# 88__3.net
KiCad netlist of a schematic drawn in Altium Designer
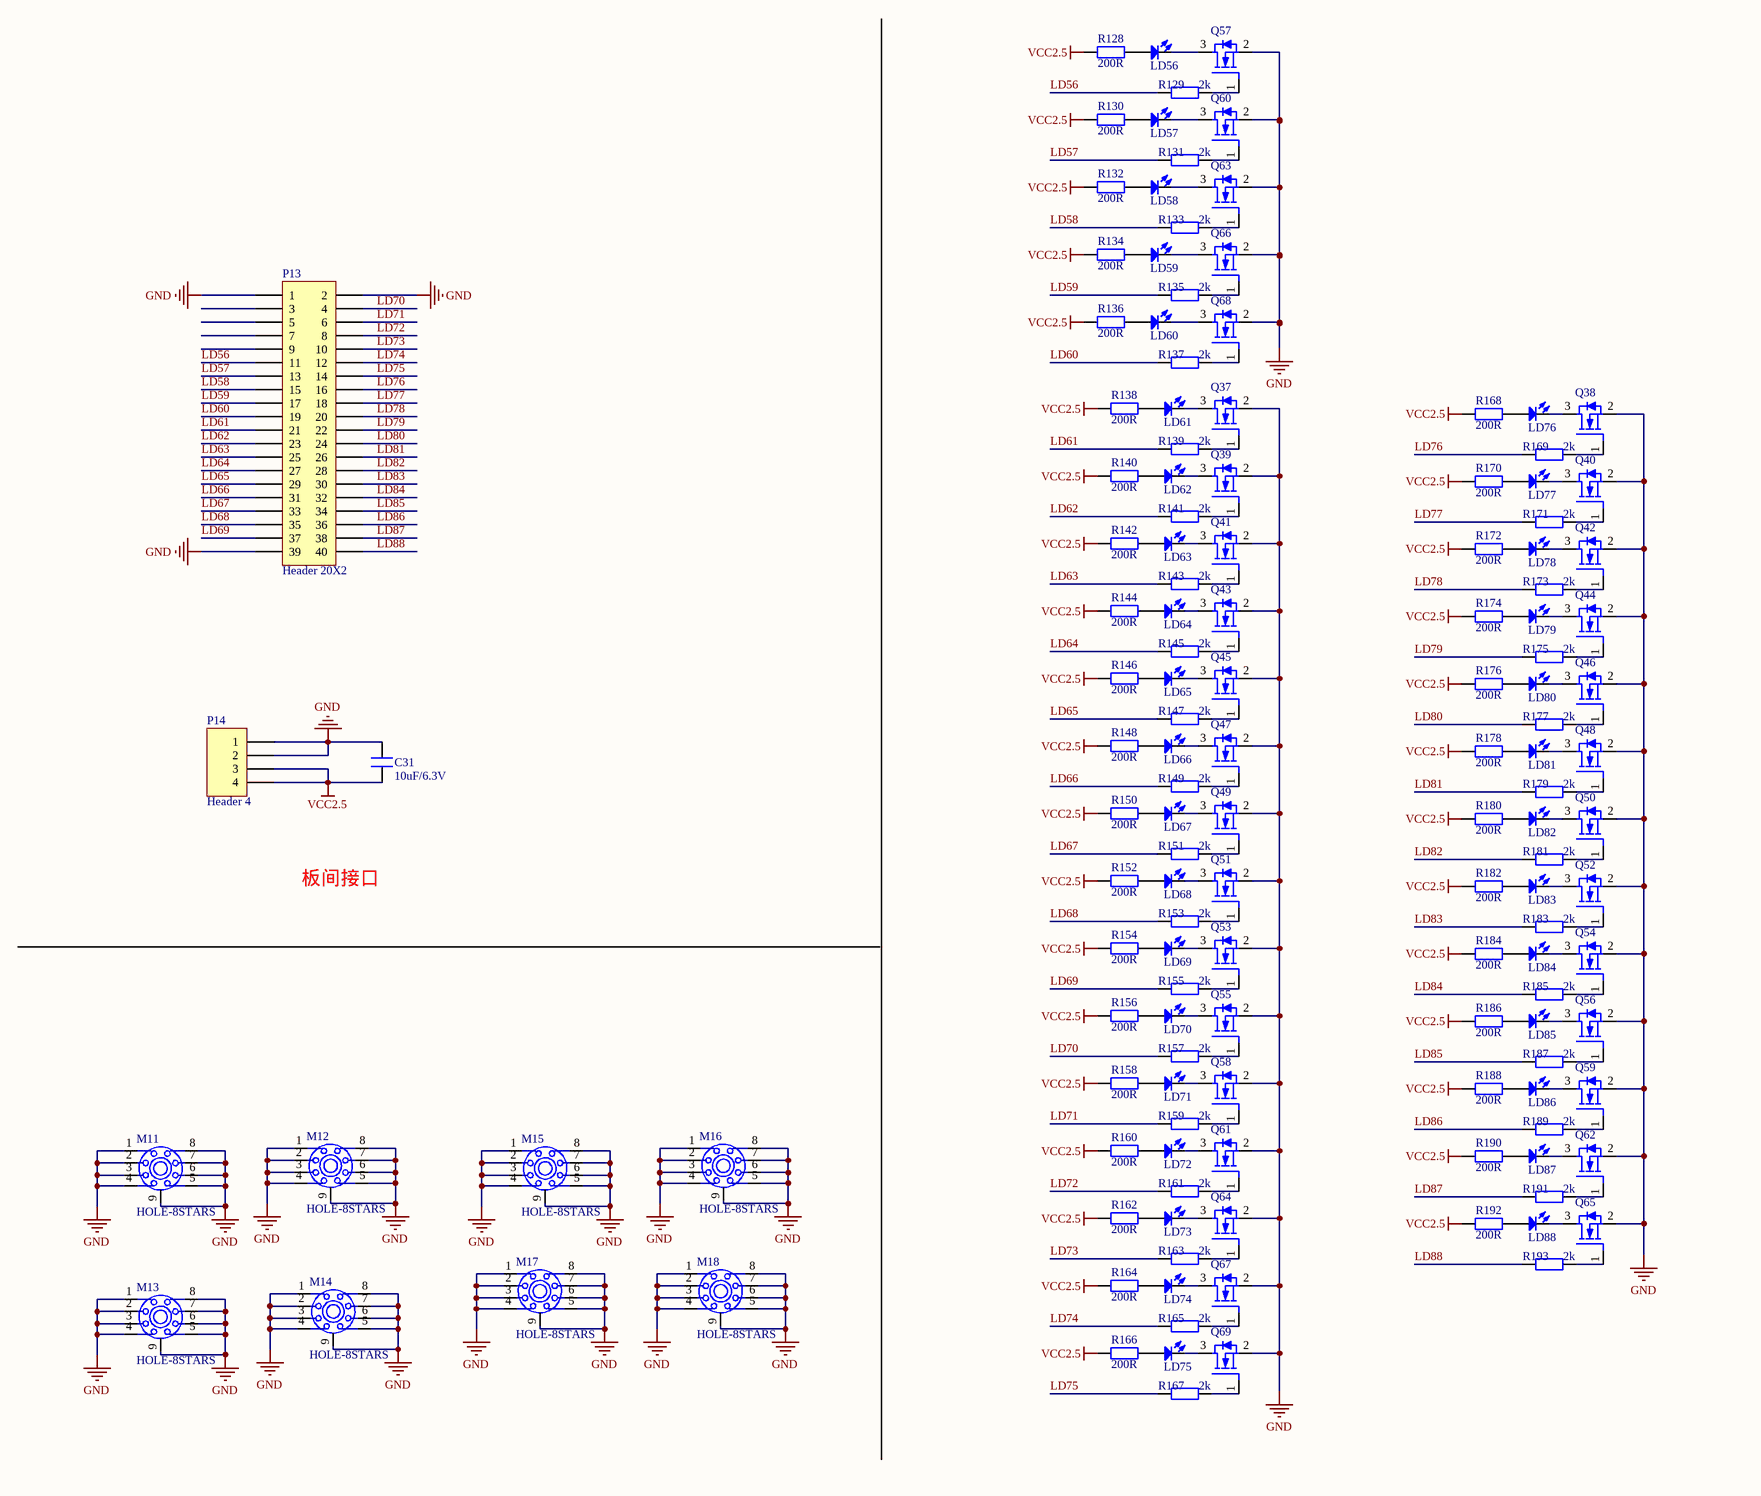
[diagram p0: 88路激光器工程_3.SchDoc, bottom]

(export (version "E")
  (design (tool "Eeschema 10.0.6"))
  (components
    (comp (ref "C31")
      (value "10uF/6.3V")
      (footprint "C0805")
      (libsource (lib "Explorer STM32F407封装库2") (part "C"))
    )
    (comp (ref "LD56") (value "LD") (footprint "LD_3P") (libsource (lib "SchLib1") (part "LD")))
    (comp (ref "LD57") (value "LD") (footprint "LD_3P") (libsource (lib "SchLib1") (part "LD")))
    (comp (ref "LD58") (value "LD") (footprint "LD_3P") (libsource (lib "SchLib1") (part "LD")))
    (comp (ref "LD59") (value "LD") (footprint "LD_3P") (libsource (lib "SchLib1") (part "LD")))
    (comp (ref "LD60") (value "LD") (footprint "LD_3P") (libsource (lib "SchLib1") (part "LD")))
    (comp (ref "LD61") (value "LD") (footprint "LD_3P") (libsource (lib "SchLib1") (part "LD")))
    (comp (ref "LD62") (value "LD") (footprint "LD_3P") (libsource (lib "SchLib1") (part "LD")))
    (comp (ref "LD63") (value "LD") (footprint "LD_3P") (libsource (lib "SchLib1") (part "LD")))
    (comp (ref "LD64") (value "LD") (footprint "LD_3P") (libsource (lib "SchLib1") (part "LD")))
    (comp (ref "LD65") (value "LD") (footprint "LD_3P") (libsource (lib "SchLib1") (part "LD")))
    (comp (ref "LD66") (value "LD") (footprint "LD_3P") (libsource (lib "SchLib1") (part "LD")))
    (comp (ref "LD67") (value "LD") (footprint "LD_3P") (libsource (lib "SchLib1") (part "LD")))
    (comp (ref "LD68") (value "LD") (footprint "LD_3P") (libsource (lib "SchLib1") (part "LD")))
    (comp (ref "LD69") (value "LD") (footprint "LD_3P") (libsource (lib "SchLib1") (part "LD")))
    (comp (ref "LD70") (value "LD") (footprint "LD_3P") (libsource (lib "SchLib1") (part "LD")))
    (comp (ref "LD71") (value "LD") (footprint "LD_3P") (libsource (lib "SchLib1") (part "LD")))
    (comp (ref "LD72") (value "LD") (footprint "LD_3P") (libsource (lib "SchLib1") (part "LD")))
    (comp (ref "LD73") (value "LD") (footprint "LD_3P") (libsource (lib "SchLib1") (part "LD")))
    (comp (ref "LD74") (value "LD") (footprint "LD_3P") (libsource (lib "SchLib1") (part "LD")))
    (comp (ref "LD75") (value "LD") (footprint "LD_3P") (libsource (lib "SchLib1") (part "LD")))
    (comp (ref "LD76") (value "LD") (footprint "LD_3P") (libsource (lib "SchLib1") (part "LD")))
    (comp (ref "LD77") (value "LD") (footprint "LD_3P") (libsource (lib "SchLib1") (part "LD")))
    (comp (ref "LD78") (value "LD") (footprint "LD_3P") (libsource (lib "SchLib1") (part "LD")))
    (comp (ref "LD79") (value "LD") (footprint "LD_3P") (libsource (lib "SchLib1") (part "LD")))
    (comp (ref "LD80") (value "LD") (footprint "LD_3P") (libsource (lib "SchLib1") (part "LD")))
    (comp (ref "LD81") (value "LD") (footprint "LD_3P") (libsource (lib "SchLib1") (part "LD")))
    (comp (ref "LD82") (value "LD") (footprint "LD_3P") (libsource (lib "SchLib1") (part "LD")))
    (comp (ref "LD83") (value "LD") (footprint "LD_3P") (libsource (lib "SchLib1") (part "LD")))
    (comp (ref "LD84") (value "LD") (footprint "LD_3P") (libsource (lib "SchLib1") (part "LD")))
    (comp (ref "LD85") (value "LD") (footprint "LD_3P") (libsource (lib "SchLib1") (part "LD")))
    (comp (ref "LD86") (value "LD") (footprint "LD_3P") (libsource (lib "SchLib1") (part "LD")))
    (comp (ref "LD87") (value "LD") (footprint "LD_3P") (libsource (lib "SchLib1") (part "LD")))
    (comp (ref "LD88") (value "LD") (footprint "LD_3P") (libsource (lib "SchLib1") (part "LD")))
    (comp (ref "M11")
      (value "HOLE-8STARS")
      (footprint "HOLE_3MM")
      (libsource (lib "TOF_SCH") (part "HOLE-8STARS"))
    )
    (comp (ref "M12")
      (value "HOLE-8STARS")
      (footprint "HOLE_3MM")
      (libsource (lib "TOF_SCH") (part "HOLE-8STARS"))
    )
    (comp (ref "M13")
      (value "HOLE-8STARS")
      (footprint "HOLE_3MM")
      (libsource (lib "TOF_SCH") (part "HOLE-8STARS"))
    )
    (comp (ref "M14")
      (value "HOLE-8STARS")
      (footprint "HOLE_3MM")
      (libsource (lib "TOF_SCH") (part "HOLE-8STARS"))
    )
    (comp (ref "M15")
      (value "HOLE-8STARS")
      (footprint "HOLE_3MM")
      (libsource (lib "TOF_SCH") (part "HOLE-8STARS"))
    )
    (comp (ref "M16")
      (value "HOLE-8STARS")
      (footprint "HOLE_3MM")
      (libsource (lib "TOF_SCH") (part "HOLE-8STARS"))
    )
    (comp (ref "M17")
      (value "HOLE-8STARS")
      (footprint "HOLE_3MM")
      (libsource (lib "TOF_SCH") (part "HOLE-8STARS"))
    )
    (comp (ref "M18")
      (value "HOLE-8STARS")
      (footprint "HOLE_3MM")
      (libsource (lib "TOF_SCH") (part "HOLE-8STARS"))
    )
    (comp (ref "P13")
      (value "Header 20X2")
      (footprint "JATG_2.0mm_2x20P_SMD")
      (description "Header, 20-Pin, Dual row")
      (fields (field (name "PUBLISHER") "Altium Limited"))
      (libsource (lib "Miscellaneous Connectors") (part "Header 20X2"))
    )
    (comp (ref "P14")
      (value "Header 4")
      (footprint "XH2.54MM_4P_立式")
      (description "Header, 4-Pin")
      (fields (field (name "PUBLISHER") "Altium Limited"))
      (libsource (lib "Miscellaneous Connectors") (part "Header 4"))
    )
    (comp (ref "Q37") (value "NMOS") (footprint "SOT23-3") (libsource (lib "88路激光器工程") (part "NMOS")))
    (comp (ref "Q38") (value "NMOS") (footprint "SOT23-3") (libsource (lib "88路激光器工程") (part "NMOS")))
    (comp (ref "Q39") (value "NMOS") (footprint "SOT23-3") (libsource (lib "88路激光器工程") (part "NMOS")))
    (comp (ref "Q40") (value "NMOS") (footprint "SOT23-3") (libsource (lib "88路激光器工程") (part "NMOS")))
    (comp (ref "Q41") (value "NMOS") (footprint "SOT23-3") (libsource (lib "88路激光器工程") (part "NMOS")))
    (comp (ref "Q42") (value "NMOS") (footprint "SOT23-3") (libsource (lib "88路激光器工程") (part "NMOS")))
    (comp (ref "Q43") (value "NMOS") (footprint "SOT23-3") (libsource (lib "88路激光器工程") (part "NMOS")))
    (comp (ref "Q44") (value "NMOS") (footprint "SOT23-3") (libsource (lib "88路激光器工程") (part "NMOS")))
    (comp (ref "Q45") (value "NMOS") (footprint "SOT23-3") (libsource (lib "88路激光器工程") (part "NMOS")))
    (comp (ref "Q46") (value "NMOS") (footprint "SOT23-3") (libsource (lib "88路激光器工程") (part "NMOS")))
    (comp (ref "Q47") (value "NMOS") (footprint "SOT23-3") (libsource (lib "88路激光器工程") (part "NMOS")))
    (comp (ref "Q48") (value "NMOS") (footprint "SOT23-3") (libsource (lib "88路激光器工程") (part "NMOS")))
    (comp (ref "Q49") (value "NMOS") (footprint "SOT23-3") (libsource (lib "88路激光器工程") (part "NMOS")))
    (comp (ref "Q50") (value "NMOS") (footprint "SOT23-3") (libsource (lib "88路激光器工程") (part "NMOS")))
    (comp (ref "Q51") (value "NMOS") (footprint "SOT23-3") (libsource (lib "88路激光器工程") (part "NMOS")))
    (comp (ref "Q52") (value "NMOS") (footprint "SOT23-3") (libsource (lib "88路激光器工程") (part "NMOS")))
    (comp (ref "Q53") (value "NMOS") (footprint "SOT23-3") (libsource (lib "88路激光器工程") (part "NMOS")))
    (comp (ref "Q54") (value "NMOS") (footprint "SOT23-3") (libsource (lib "88路激光器工程") (part "NMOS")))
    (comp (ref "Q55") (value "NMOS") (footprint "SOT23-3") (libsource (lib "88路激光器工程") (part "NMOS")))
    (comp (ref "Q56") (value "NMOS") (footprint "SOT23-3") (libsource (lib "88路激光器工程") (part "NMOS")))
    (comp (ref "Q57") (value "NMOS") (footprint "SOT23-3") (libsource (lib "88路激光器工程") (part "NMOS")))
    (comp (ref "Q58") (value "NMOS") (footprint "SOT23-3") (libsource (lib "88路激光器工程") (part "NMOS")))
    (comp (ref "Q59") (value "NMOS") (footprint "SOT23-3") (libsource (lib "88路激光器工程") (part "NMOS")))
    (comp (ref "Q60") (value "NMOS") (footprint "SOT23-3") (libsource (lib "88路激光器工程") (part "NMOS")))
    (comp (ref "Q61") (value "NMOS") (footprint "SOT23-3") (libsource (lib "88路激光器工程") (part "NMOS")))
    (comp (ref "Q62") (value "NMOS") (footprint "SOT23-3") (libsource (lib "88路激光器工程") (part "NMOS")))
    (comp (ref "Q63") (value "NMOS") (footprint "SOT23-3") (libsource (lib "88路激光器工程") (part "NMOS")))
    (comp (ref "Q64") (value "NMOS") (footprint "SOT23-3") (libsource (lib "88路激光器工程") (part "NMOS")))
    (comp (ref "Q65") (value "NMOS") (footprint "SOT23-3") (libsource (lib "88路激光器工程") (part "NMOS")))
    (comp (ref "Q66") (value "NMOS") (footprint "SOT23-3") (libsource (lib "88路激光器工程") (part "NMOS")))
    (comp (ref "Q67") (value "NMOS") (footprint "SOT23-3") (libsource (lib "88路激光器工程") (part "NMOS")))
    (comp (ref "Q68") (value "NMOS") (footprint "SOT23-3") (libsource (lib "88路激光器工程") (part "NMOS")))
    (comp (ref "Q69") (value "NMOS") (footprint "SOT23-3") (libsource (lib "88路激光器工程") (part "NMOS")))
    (comp (ref "R128")
      (value "200R")
      (footprint "R0805")
      (description "Resistor")
      (fields (field (name "PUBLISHER") "Altium Limited"))
      (libsource (lib "Miscellaneous Devices") (part "Res2"))
    )
    (comp (ref "R129")
      (value "2k")
      (footprint "R0805")
      (description "Resistor")
      (fields (field (name "PUBLISHER") "Altium Limited"))
      (libsource (lib "Miscellaneous Devices") (part "Res2"))
    )
    (comp (ref "R130")
      (value "200R")
      (footprint "R0805")
      (description "Resistor")
      (fields (field (name "PUBLISHER") "Altium Limited"))
      (libsource (lib "Miscellaneous Devices") (part "Res2"))
    )
    (comp (ref "R131")
      (value "2k")
      (footprint "R0805")
      (description "Resistor")
      (fields (field (name "PUBLISHER") "Altium Limited"))
      (libsource (lib "Miscellaneous Devices") (part "Res2"))
    )
    (comp (ref "R132")
      (value "200R")
      (footprint "R0805")
      (description "Resistor")
      (fields (field (name "PUBLISHER") "Altium Limited"))
      (libsource (lib "Miscellaneous Devices") (part "Res2"))
    )
    (comp (ref "R133")
      (value "2k")
      (footprint "R0805")
      (description "Resistor")
      (fields (field (name "PUBLISHER") "Altium Limited"))
      (libsource (lib "Miscellaneous Devices") (part "Res2"))
    )
    (comp (ref "R134")
      (value "200R")
      (footprint "R0805")
      (description "Resistor")
      (fields (field (name "PUBLISHER") "Altium Limited"))
      (libsource (lib "Miscellaneous Devices") (part "Res2"))
    )
    (comp (ref "R135")
      (value "2k")
      (footprint "R0805")
      (description "Resistor")
      (fields (field (name "PUBLISHER") "Altium Limited"))
      (libsource (lib "Miscellaneous Devices") (part "Res2"))
    )
    (comp (ref "R136")
      (value "200R")
      (footprint "R0805")
      (description "Resistor")
      (fields (field (name "PUBLISHER") "Altium Limited"))
      (libsource (lib "Miscellaneous Devices") (part "Res2"))
    )
    (comp (ref "R137")
      (value "2k")
      (footprint "R0805")
      (description "Resistor")
      (fields (field (name "PUBLISHER") "Altium Limited"))
      (libsource (lib "Miscellaneous Devices") (part "Res2"))
    )
    (comp (ref "R138")
      (value "200R")
      (footprint "R0805")
      (description "Resistor")
      (fields (field (name "PUBLISHER") "Altium Limited"))
      (libsource (lib "Miscellaneous Devices") (part "Res2"))
    )
    (comp (ref "R139")
      (value "2k")
      (footprint "R0805")
      (description "Resistor")
      (fields (field (name "PUBLISHER") "Altium Limited"))
      (libsource (lib "Miscellaneous Devices") (part "Res2"))
    )
    (comp (ref "R140")
      (value "200R")
      (footprint "R0805")
      (description "Resistor")
      (fields (field (name "PUBLISHER") "Altium Limited"))
      (libsource (lib "Miscellaneous Devices") (part "Res2"))
    )
    (comp (ref "R141")
      (value "2k")
      (footprint "R0805")
      (description "Resistor")
      (fields (field (name "PUBLISHER") "Altium Limited"))
      (libsource (lib "Miscellaneous Devices") (part "Res2"))
    )
    (comp (ref "R142")
      (value "200R")
      (footprint "R0805")
      (description "Resistor")
      (fields (field (name "PUBLISHER") "Altium Limited"))
      (libsource (lib "Miscellaneous Devices") (part "Res2"))
    )
    (comp (ref "R143")
      (value "2k")
      (footprint "R0805")
      (description "Resistor")
      (fields (field (name "PUBLISHER") "Altium Limited"))
      (libsource (lib "Miscellaneous Devices") (part "Res2"))
    )
    (comp (ref "R144")
      (value "200R")
      (footprint "R0805")
      (description "Resistor")
      (fields (field (name "PUBLISHER") "Altium Limited"))
      (libsource (lib "Miscellaneous Devices") (part "Res2"))
    )
    (comp (ref "R145")
      (value "2k")
      (footprint "R0805")
      (description "Resistor")
      (fields (field (name "PUBLISHER") "Altium Limited"))
      (libsource (lib "Miscellaneous Devices") (part "Res2"))
    )
    (comp (ref "R146")
      (value "200R")
      (footprint "R0805")
      (description "Resistor")
      (fields (field (name "PUBLISHER") "Altium Limited"))
      (libsource (lib "Miscellaneous Devices") (part "Res2"))
    )
    (comp (ref "R147")
      (value "2k")
      (footprint "R0805")
      (description "Resistor")
      (fields (field (name "PUBLISHER") "Altium Limited"))
      (libsource (lib "Miscellaneous Devices") (part "Res2"))
    )
    (comp (ref "R148")
      (value "200R")
      (footprint "R0805")
      (description "Resistor")
      (fields (field (name "PUBLISHER") "Altium Limited"))
      (libsource (lib "Miscellaneous Devices") (part "Res2"))
    )
    (comp (ref "R149")
      (value "2k")
      (footprint "R0805")
      (description "Resistor")
      (fields (field (name "PUBLISHER") "Altium Limited"))
      (libsource (lib "Miscellaneous Devices") (part "Res2"))
    )
    (comp (ref "R150")
      (value "200R")
      (footprint "R0805")
      (description "Resistor")
      (fields (field (name "PUBLISHER") "Altium Limited"))
      (libsource (lib "Miscellaneous Devices") (part "Res2"))
    )
    (comp (ref "R151")
      (value "2k")
      (footprint "R0805")
      (description "Resistor")
      (fields (field (name "PUBLISHER") "Altium Limited"))
      (libsource (lib "Miscellaneous Devices") (part "Res2"))
    )
    (comp (ref "R152")
      (value "200R")
      (footprint "R0805")
      (description "Resistor")
      (fields (field (name "PUBLISHER") "Altium Limited"))
      (libsource (lib "Miscellaneous Devices") (part "Res2"))
    )
    (comp (ref "R153")
      (value "2k")
      (footprint "R0805")
      (description "Resistor")
      (fields (field (name "PUBLISHER") "Altium Limited"))
      (libsource (lib "Miscellaneous Devices") (part "Res2"))
    )
    (comp (ref "R154")
      (value "200R")
      (footprint "R0805")
      (description "Resistor")
      (fields (field (name "PUBLISHER") "Altium Limited"))
      (libsource (lib "Miscellaneous Devices") (part "Res2"))
    )
    (comp (ref "R155")
      (value "2k")
      (footprint "R0805")
      (description "Resistor")
      (fields (field (name "PUBLISHER") "Altium Limited"))
      (libsource (lib "Miscellaneous Devices") (part "Res2"))
    )
    (comp (ref "R156")
      (value "200R")
      (footprint "R0805")
      (description "Resistor")
      (fields (field (name "PUBLISHER") "Altium Limited"))
      (libsource (lib "Miscellaneous Devices") (part "Res2"))
    )
    (comp (ref "R157")
      (value "2k")
      (footprint "R0805")
      (description "Resistor")
      (fields (field (name "PUBLISHER") "Altium Limited"))
      (libsource (lib "Miscellaneous Devices") (part "Res2"))
    )
    (comp (ref "R158")
      (value "200R")
      (footprint "R0805")
      (description "Resistor")
      (fields (field (name "PUBLISHER") "Altium Limited"))
      (libsource (lib "Miscellaneous Devices") (part "Res2"))
    )
    (comp (ref "R159")
      (value "2k")
      (footprint "R0805")
      (description "Resistor")
      (fields (field (name "PUBLISHER") "Altium Limited"))
      (libsource (lib "Miscellaneous Devices") (part "Res2"))
    )
    (comp (ref "R160")
      (value "200R")
      (footprint "R0805")
      (description "Resistor")
      (fields (field (name "PUBLISHER") "Altium Limited"))
      (libsource (lib "Miscellaneous Devices") (part "Res2"))
    )
    (comp (ref "R161")
      (value "2k")
      (footprint "R0805")
      (description "Resistor")
      (fields (field (name "PUBLISHER") "Altium Limited"))
      (libsource (lib "Miscellaneous Devices") (part "Res2"))
    )
    (comp (ref "R162")
      (value "200R")
      (footprint "R0805")
      (description "Resistor")
      (fields (field (name "PUBLISHER") "Altium Limited"))
      (libsource (lib "Miscellaneous Devices") (part "Res2"))
    )
    (comp (ref "R163")
      (value "2k")
      (footprint "R0805")
      (description "Resistor")
      (fields (field (name "PUBLISHER") "Altium Limited"))
      (libsource (lib "Miscellaneous Devices") (part "Res2"))
    )
    (comp (ref "R164")
      (value "200R")
      (footprint "R0805")
      (description "Resistor")
      (fields (field (name "PUBLISHER") "Altium Limited"))
      (libsource (lib "Miscellaneous Devices") (part "Res2"))
    )
    (comp (ref "R165")
      (value "2k")
      (footprint "R0805")
      (description "Resistor")
      (fields (field (name "PUBLISHER") "Altium Limited"))
      (libsource (lib "Miscellaneous Devices") (part "Res2"))
    )
    (comp (ref "R166")
      (value "200R")
      (footprint "R0805")
      (description "Resistor")
      (fields (field (name "PUBLISHER") "Altium Limited"))
      (libsource (lib "Miscellaneous Devices") (part "Res2"))
    )
    (comp (ref "R167")
      (value "2k")
      (footprint "R0805")
      (description "Resistor")
      (fields (field (name "PUBLISHER") "Altium Limited"))
      (libsource (lib "Miscellaneous Devices") (part "Res2"))
    )
    (comp (ref "R168")
      (value "200R")
      (footprint "R0805")
      (description "Resistor")
      (fields (field (name "PUBLISHER") "Altium Limited"))
      (libsource (lib "Miscellaneous Devices") (part "Res2"))
    )
    (comp (ref "R169")
      (value "2k")
      (footprint "R0805")
      (description "Resistor")
      (fields (field (name "PUBLISHER") "Altium Limited"))
      (libsource (lib "Miscellaneous Devices") (part "Res2"))
    )
    (comp (ref "R170")
      (value "200R")
      (footprint "R0805")
      (description "Resistor")
      (fields (field (name "PUBLISHER") "Altium Limited"))
      (libsource (lib "Miscellaneous Devices") (part "Res2"))
    )
    (comp (ref "R171")
      (value "2k")
      (footprint "R0805")
      (description "Resistor")
      (fields (field (name "PUBLISHER") "Altium Limited"))
      (libsource (lib "Miscellaneous Devices") (part "Res2"))
    )
    (comp (ref "R172")
      (value "200R")
      (footprint "R0805")
      (description "Resistor")
      (fields (field (name "PUBLISHER") "Altium Limited"))
      (libsource (lib "Miscellaneous Devices") (part "Res2"))
    )
    (comp (ref "R173")
      (value "2k")
      (footprint "R0805")
      (description "Resistor")
      (fields (field (name "PUBLISHER") "Altium Limited"))
      (libsource (lib "Miscellaneous Devices") (part "Res2"))
    )
    (comp (ref "R174")
      (value "200R")
      (footprint "R0805")
      (description "Resistor")
      (fields (field (name "PUBLISHER") "Altium Limited"))
      (libsource (lib "Miscellaneous Devices") (part "Res2"))
    )
    (comp (ref "R175")
      (value "2k")
      (footprint "R0805")
      (description "Resistor")
      (fields (field (name "PUBLISHER") "Altium Limited"))
      (libsource (lib "Miscellaneous Devices") (part "Res2"))
    )
    (comp (ref "R176")
      (value "200R")
      (footprint "R0805")
      (description "Resistor")
      (fields (field (name "PUBLISHER") "Altium Limited"))
      (libsource (lib "Miscellaneous Devices") (part "Res2"))
    )
    (comp (ref "R177")
      (value "2k")
      (footprint "R0805")
      (description "Resistor")
      (fields (field (name "PUBLISHER") "Altium Limited"))
      (libsource (lib "Miscellaneous Devices") (part "Res2"))
    )
    (comp (ref "R178")
      (value "200R")
      (footprint "R0805")
      (description "Resistor")
      (fields (field (name "PUBLISHER") "Altium Limited"))
      (libsource (lib "Miscellaneous Devices") (part "Res2"))
    )
    (comp (ref "R179")
      (value "2k")
      (footprint "R0805")
      (description "Resistor")
      (fields (field (name "PUBLISHER") "Altium Limited"))
      (libsource (lib "Miscellaneous Devices") (part "Res2"))
    )
    (comp (ref "R180")
      (value "200R")
      (footprint "R0805")
      (description "Resistor")
      (fields (field (name "PUBLISHER") "Altium Limited"))
      (libsource (lib "Miscellaneous Devices") (part "Res2"))
    )
    (comp (ref "R181")
      (value "2k")
      (footprint "R0805")
      (description "Resistor")
      (fields (field (name "PUBLISHER") "Altium Limited"))
      (libsource (lib "Miscellaneous Devices") (part "Res2"))
    )
    (comp (ref "R182")
      (value "200R")
      (footprint "R0805")
      (description "Resistor")
      (fields (field (name "PUBLISHER") "Altium Limited"))
      (libsource (lib "Miscellaneous Devices") (part "Res2"))
    )
    (comp (ref "R183")
      (value "2k")
      (footprint "R0805")
      (description "Resistor")
      (fields (field (name "PUBLISHER") "Altium Limited"))
      (libsource (lib "Miscellaneous Devices") (part "Res2"))
    )
    (comp (ref "R184")
      (value "200R")
      (footprint "R0805")
      (description "Resistor")
      (fields (field (name "PUBLISHER") "Altium Limited"))
      (libsource (lib "Miscellaneous Devices") (part "Res2"))
    )
    (comp (ref "R185")
      (value "2k")
      (footprint "R0805")
      (description "Resistor")
      (fields (field (name "PUBLISHER") "Altium Limited"))
      (libsource (lib "Miscellaneous Devices") (part "Res2"))
    )
    (comp (ref "R186")
      (value "200R")
      (footprint "R0805")
      (description "Resistor")
      (fields (field (name "PUBLISHER") "Altium Limited"))
      (libsource (lib "Miscellaneous Devices") (part "Res2"))
    )
    (comp (ref "R187")
      (value "2k")
      (footprint "R0805")
      (description "Resistor")
      (fields (field (name "PUBLISHER") "Altium Limited"))
      (libsource (lib "Miscellaneous Devices") (part "Res2"))
    )
    (comp (ref "R188")
      (value "200R")
      (footprint "R0805")
      (description "Resistor")
      (fields (field (name "PUBLISHER") "Altium Limited"))
      (libsource (lib "Miscellaneous Devices") (part "Res2"))
    )
    (comp (ref "R189")
      (value "2k")
      (footprint "R0805")
      (description "Resistor")
      (fields (field (name "PUBLISHER") "Altium Limited"))
      (libsource (lib "Miscellaneous Devices") (part "Res2"))
    )
    (comp (ref "R190")
      (value "200R")
      (footprint "R0805")
      (description "Resistor")
      (fields (field (name "PUBLISHER") "Altium Limited"))
      (libsource (lib "Miscellaneous Devices") (part "Res2"))
    )
    (comp (ref "R191")
      (value "2k")
      (footprint "R0805")
      (description "Resistor")
      (fields (field (name "PUBLISHER") "Altium Limited"))
      (libsource (lib "Miscellaneous Devices") (part "Res2"))
    )
    (comp (ref "R192")
      (value "200R")
      (footprint "R0805")
      (description "Resistor")
      (fields (field (name "PUBLISHER") "Altium Limited"))
      (libsource (lib "Miscellaneous Devices") (part "Res2"))
    )
    (comp (ref "R193")
      (value "2k")
      (footprint "R0805")
      (description "Resistor")
      (fields (field (name "PUBLISHER") "Altium Limited"))
      (libsource (lib "Miscellaneous Devices") (part "Res2"))
    )
  )
  (nets
    (net (code "1") (name "/LD56") (class "Default")
      (node (ref "P13") (pin "11") (pinfunction "11_11") (pintype "passive"))
      (node (ref "R129") (pin "2") (pinfunction "2_2") (pintype "passive"))
    )
    (net (code "2") (name "/LD57") (class "Default")
      (node (ref "P13") (pin "13") (pinfunction "13_13") (pintype "passive"))
      (node (ref "R131") (pin "2") (pinfunction "2_2") (pintype "passive"))
    )
    (net (code "3") (name "/LD58") (class "Default")
      (node (ref "P13") (pin "15") (pinfunction "15_15") (pintype "passive"))
      (node (ref "R133") (pin "2") (pinfunction "2_2") (pintype "passive"))
    )
    (net (code "4") (name "/LD59") (class "Default")
      (node (ref "P13") (pin "17") (pinfunction "17_17") (pintype "passive"))
      (node (ref "R135") (pin "2") (pinfunction "2_2") (pintype "passive"))
    )
    (net (code "5") (name "/LD60") (class "Default")
      (node (ref "P13") (pin "19") (pinfunction "19_19") (pintype "passive"))
      (node (ref "R137") (pin "2") (pinfunction "2_2") (pintype "passive"))
    )
    (net (code "6") (name "/LD61") (class "Default")
      (node (ref "P13") (pin "21") (pinfunction "21_21") (pintype "passive"))
      (node (ref "R139") (pin "2") (pinfunction "2_2") (pintype "passive"))
    )
    (net (code "7") (name "/LD62") (class "Default")
      (node (ref "P13") (pin "23") (pinfunction "23_23") (pintype "passive"))
      (node (ref "R141") (pin "2") (pinfunction "2_2") (pintype "passive"))
    )
    (net (code "8") (name "/LD63") (class "Default")
      (node (ref "P13") (pin "25") (pinfunction "25_25") (pintype "passive"))
      (node (ref "R143") (pin "2") (pinfunction "2_2") (pintype "passive"))
    )
    (net (code "9") (name "/LD64") (class "Default")
      (node (ref "P13") (pin "27") (pinfunction "27_27") (pintype "passive"))
      (node (ref "R145") (pin "2") (pinfunction "2_2") (pintype "passive"))
    )
    (net (code "10") (name "/LD65") (class "Default")
      (node (ref "P13") (pin "29") (pinfunction "29_29") (pintype "passive"))
      (node (ref "R147") (pin "2") (pinfunction "2_2") (pintype "passive"))
    )
    (net (code "11") (name "/LD66") (class "Default")
      (node (ref "P13") (pin "31") (pinfunction "31_31") (pintype "passive"))
      (node (ref "R149") (pin "2") (pinfunction "2_2") (pintype "passive"))
    )
    (net (code "12") (name "/LD67") (class "Default")
      (node (ref "P13") (pin "33") (pinfunction "33_33") (pintype "passive"))
      (node (ref "R151") (pin "2") (pinfunction "2_2") (pintype "passive"))
    )
    (net (code "13") (name "/LD68") (class "Default")
      (node (ref "P13") (pin "35") (pinfunction "35_35") (pintype "passive"))
      (node (ref "R153") (pin "2") (pinfunction "2_2") (pintype "passive"))
    )
    (net (code "14") (name "/LD69") (class "Default")
      (node (ref "P13") (pin "37") (pinfunction "37_37") (pintype "passive"))
      (node (ref "R155") (pin "2") (pinfunction "2_2") (pintype "passive"))
    )
    (net (code "15") (name "/LD70") (class "Default")
      (node (ref "P13") (pin "4") (pinfunction "4_4") (pintype "passive"))
      (node (ref "R157") (pin "2") (pinfunction "2_2") (pintype "passive"))
    )
    (net (code "16") (name "/LD71") (class "Default")
      (node (ref "P13") (pin "6") (pinfunction "6_6") (pintype "passive"))
      (node (ref "R159") (pin "2") (pinfunction "2_2") (pintype "passive"))
    )
    (net (code "17") (name "/LD72") (class "Default")
      (node (ref "P13") (pin "8") (pinfunction "8_8") (pintype "passive"))
      (node (ref "R161") (pin "2") (pinfunction "2_2") (pintype "passive"))
    )
    (net (code "18") (name "/LD73") (class "Default")
      (node (ref "P13") (pin "10") (pinfunction "10_10") (pintype "passive"))
      (node (ref "R163") (pin "2") (pinfunction "2_2") (pintype "passive"))
    )
    (net (code "19") (name "/LD74") (class "Default")
      (node (ref "P13") (pin "12") (pinfunction "12_12") (pintype "passive"))
      (node (ref "R165") (pin "2") (pinfunction "2_2") (pintype "passive"))
    )
    (net (code "20") (name "/LD75") (class "Default")
      (node (ref "P13") (pin "14") (pinfunction "14_14") (pintype "passive"))
      (node (ref "R167") (pin "2") (pinfunction "2_2") (pintype "passive"))
    )
    (net (code "21") (name "/LD76") (class "Default")
      (node (ref "P13") (pin "16") (pinfunction "16_16") (pintype "passive"))
      (node (ref "R169") (pin "2") (pinfunction "2_2") (pintype "passive"))
    )
    (net (code "22") (name "/LD77") (class "Default")
      (node (ref "P13") (pin "18") (pinfunction "18_18") (pintype "passive"))
      (node (ref "R171") (pin "2") (pinfunction "2_2") (pintype "passive"))
    )
    (net (code "23") (name "/LD78") (class "Default")
      (node (ref "P13") (pin "20") (pinfunction "20_20") (pintype "passive"))
      (node (ref "R173") (pin "2") (pinfunction "2_2") (pintype "passive"))
    )
    (net (code "24") (name "/LD79") (class "Default")
      (node (ref "P13") (pin "22") (pinfunction "22_22") (pintype "passive"))
      (node (ref "R175") (pin "2") (pinfunction "2_2") (pintype "passive"))
    )
    (net (code "25") (name "/LD80") (class "Default")
      (node (ref "P13") (pin "24") (pinfunction "24_24") (pintype "passive"))
      (node (ref "R177") (pin "2") (pinfunction "2_2") (pintype "passive"))
    )
    (net (code "26") (name "/LD81") (class "Default")
      (node (ref "P13") (pin "26") (pinfunction "26_26") (pintype "passive"))
      (node (ref "R179") (pin "2") (pinfunction "2_2") (pintype "passive"))
    )
    (net (code "27") (name "/LD82") (class "Default")
      (node (ref "P13") (pin "28") (pinfunction "28_28") (pintype "passive"))
      (node (ref "R181") (pin "2") (pinfunction "2_2") (pintype "passive"))
    )
    (net (code "28") (name "/LD83") (class "Default")
      (node (ref "P13") (pin "30") (pinfunction "30_30") (pintype "passive"))
      (node (ref "R183") (pin "2") (pinfunction "2_2") (pintype "passive"))
    )
    (net (code "29") (name "/LD84") (class "Default")
      (node (ref "P13") (pin "32") (pinfunction "32_32") (pintype "passive"))
      (node (ref "R185") (pin "2") (pinfunction "2_2") (pintype "passive"))
    )
    (net (code "30") (name "/LD85") (class "Default")
      (node (ref "P13") (pin "34") (pinfunction "34_34") (pintype "passive"))
      (node (ref "R187") (pin "2") (pinfunction "2_2") (pintype "passive"))
    )
    (net (code "31") (name "/LD86") (class "Default")
      (node (ref "P13") (pin "36") (pinfunction "36_36") (pintype "passive"))
      (node (ref "R189") (pin "2") (pinfunction "2_2") (pintype "passive"))
    )
    (net (code "32") (name "/LD87") (class "Default")
      (node (ref "P13") (pin "38") (pinfunction "38_38") (pintype "passive"))
      (node (ref "R191") (pin "2") (pinfunction "2_2") (pintype "passive"))
    )
    (net (code "33") (name "/LD88") (class "Default")
      (node (ref "P13") (pin "40") (pinfunction "40_40") (pintype "passive"))
      (node (ref "R193") (pin "2") (pinfunction "2_2") (pintype "passive"))
    )
    (net (code "34") (name "GND") (class "Default")
      (node (ref "C31") (pin "2") (pintype "passive"))
      (node (ref "M11") (pin "1") (pinfunction "1_1") (pintype "passive"))
      (node (ref "M11") (pin "2") (pinfunction "2_2") (pintype "passive"))
      (node (ref "M11") (pin "3") (pinfunction "3_3") (pintype "passive"))
      (node (ref "M11") (pin "4") (pinfunction "4_4") (pintype "passive"))
      (node (ref "M11") (pin "5") (pinfunction "5_5") (pintype "passive"))
      (node (ref "M11") (pin "6") (pinfunction "6_6") (pintype "passive"))
      (node (ref "M11") (pin "7") (pinfunction "7_7") (pintype "passive"))
      (node (ref "M11") (pin "8") (pinfunction "8_8") (pintype "passive"))
      (node (ref "M11") (pin "9") (pinfunction "9_9") (pintype "passive"))
      (node (ref "M12") (pin "1") (pinfunction "1_1") (pintype "passive"))
      (node (ref "M12") (pin "2") (pinfunction "2_2") (pintype "passive"))
      (node (ref "M12") (pin "3") (pinfunction "3_3") (pintype "passive"))
      (node (ref "M12") (pin "4") (pinfunction "4_4") (pintype "passive"))
      (node (ref "M12") (pin "5") (pinfunction "5_5") (pintype "passive"))
      (node (ref "M12") (pin "6") (pinfunction "6_6") (pintype "passive"))
      (node (ref "M12") (pin "7") (pinfunction "7_7") (pintype "passive"))
      (node (ref "M12") (pin "8") (pinfunction "8_8") (pintype "passive"))
      (node (ref "M12") (pin "9") (pinfunction "9_9") (pintype "passive"))
      (node (ref "M13") (pin "1") (pinfunction "1_1") (pintype "passive"))
      (node (ref "M13") (pin "2") (pinfunction "2_2") (pintype "passive"))
      (node (ref "M13") (pin "3") (pinfunction "3_3") (pintype "passive"))
      (node (ref "M13") (pin "4") (pinfunction "4_4") (pintype "passive"))
      (node (ref "M13") (pin "5") (pinfunction "5_5") (pintype "passive"))
      (node (ref "M13") (pin "6") (pinfunction "6_6") (pintype "passive"))
      (node (ref "M13") (pin "7") (pinfunction "7_7") (pintype "passive"))
      (node (ref "M13") (pin "8") (pinfunction "8_8") (pintype "passive"))
      (node (ref "M13") (pin "9") (pinfunction "9_9") (pintype "passive"))
      (node (ref "M14") (pin "1") (pinfunction "1_1") (pintype "passive"))
      (node (ref "M14") (pin "2") (pinfunction "2_2") (pintype "passive"))
      (node (ref "M14") (pin "3") (pinfunction "3_3") (pintype "passive"))
      (node (ref "M14") (pin "4") (pinfunction "4_4") (pintype "passive"))
      (node (ref "M14") (pin "5") (pinfunction "5_5") (pintype "passive"))
      (node (ref "M14") (pin "6") (pinfunction "6_6") (pintype "passive"))
      (node (ref "M14") (pin "7") (pinfunction "7_7") (pintype "passive"))
      (node (ref "M14") (pin "8") (pinfunction "8_8") (pintype "passive"))
      (node (ref "M14") (pin "9") (pinfunction "9_9") (pintype "passive"))
      (node (ref "M15") (pin "1") (pinfunction "1_1") (pintype "passive"))
      (node (ref "M15") (pin "2") (pinfunction "2_2") (pintype "passive"))
      (node (ref "M15") (pin "3") (pinfunction "3_3") (pintype "passive"))
      (node (ref "M15") (pin "4") (pinfunction "4_4") (pintype "passive"))
      (node (ref "M15") (pin "5") (pinfunction "5_5") (pintype "passive"))
      (node (ref "M15") (pin "6") (pinfunction "6_6") (pintype "passive"))
      (node (ref "M15") (pin "7") (pinfunction "7_7") (pintype "passive"))
      (node (ref "M15") (pin "8") (pinfunction "8_8") (pintype "passive"))
      (node (ref "M15") (pin "9") (pinfunction "9_9") (pintype "passive"))
      (node (ref "M16") (pin "1") (pinfunction "1_1") (pintype "passive"))
      (node (ref "M16") (pin "2") (pinfunction "2_2") (pintype "passive"))
      (node (ref "M16") (pin "3") (pinfunction "3_3") (pintype "passive"))
      (node (ref "M16") (pin "4") (pinfunction "4_4") (pintype "passive"))
      (node (ref "M16") (pin "5") (pinfunction "5_5") (pintype "passive"))
      (node (ref "M16") (pin "6") (pinfunction "6_6") (pintype "passive"))
      (node (ref "M16") (pin "7") (pinfunction "7_7") (pintype "passive"))
      (node (ref "M16") (pin "8") (pinfunction "8_8") (pintype "passive"))
      (node (ref "M16") (pin "9") (pinfunction "9_9") (pintype "passive"))
      (node (ref "M17") (pin "1") (pinfunction "1_1") (pintype "passive"))
      (node (ref "M17") (pin "2") (pinfunction "2_2") (pintype "passive"))
      (node (ref "M17") (pin "3") (pinfunction "3_3") (pintype "passive"))
      (node (ref "M17") (pin "4") (pinfunction "4_4") (pintype "passive"))
      (node (ref "M17") (pin "5") (pinfunction "5_5") (pintype "passive"))
      (node (ref "M17") (pin "6") (pinfunction "6_6") (pintype "passive"))
      (node (ref "M17") (pin "7") (pinfunction "7_7") (pintype "passive"))
      (node (ref "M17") (pin "8") (pinfunction "8_8") (pintype "passive"))
      (node (ref "M17") (pin "9") (pinfunction "9_9") (pintype "passive"))
      (node (ref "M18") (pin "1") (pinfunction "1_1") (pintype "passive"))
      (node (ref "M18") (pin "2") (pinfunction "2_2") (pintype "passive"))
      (node (ref "M18") (pin "3") (pinfunction "3_3") (pintype "passive"))
      (node (ref "M18") (pin "4") (pinfunction "4_4") (pintype "passive"))
      (node (ref "M18") (pin "5") (pinfunction "5_5") (pintype "passive"))
      (node (ref "M18") (pin "6") (pinfunction "6_6") (pintype "passive"))
      (node (ref "M18") (pin "7") (pinfunction "7_7") (pintype "passive"))
      (node (ref "M18") (pin "8") (pinfunction "8_8") (pintype "passive"))
      (node (ref "M18") (pin "9") (pinfunction "9_9") (pintype "passive"))
      (node (ref "P13") (pin "1") (pinfunction "1_1") (pintype "passive"))
      (node (ref "P13") (pin "2") (pinfunction "2_2") (pintype "passive"))
      (node (ref "P13") (pin "39") (pinfunction "39_39") (pintype "passive"))
      (node (ref "P14") (pin "1") (pinfunction "1_1") (pintype "passive"))
      (node (ref "P14") (pin "2") (pinfunction "2_2") (pintype "passive"))
      (node (ref "Q37") (pin "2") (pinfunction "SOURCE_2") (pintype "passive"))
      (node (ref "Q38") (pin "2") (pinfunction "SOURCE_2") (pintype "passive"))
      (node (ref "Q39") (pin "2") (pinfunction "SOURCE_2") (pintype "passive"))
      (node (ref "Q40") (pin "2") (pinfunction "SOURCE_2") (pintype "passive"))
      (node (ref "Q41") (pin "2") (pinfunction "SOURCE_2") (pintype "passive"))
      (node (ref "Q42") (pin "2") (pinfunction "SOURCE_2") (pintype "passive"))
      (node (ref "Q43") (pin "2") (pinfunction "SOURCE_2") (pintype "passive"))
      (node (ref "Q44") (pin "2") (pinfunction "SOURCE_2") (pintype "passive"))
      (node (ref "Q45") (pin "2") (pinfunction "SOURCE_2") (pintype "passive"))
      (node (ref "Q46") (pin "2") (pinfunction "SOURCE_2") (pintype "passive"))
      (node (ref "Q47") (pin "2") (pinfunction "SOURCE_2") (pintype "passive"))
      (node (ref "Q48") (pin "2") (pinfunction "SOURCE_2") (pintype "passive"))
      (node (ref "Q49") (pin "2") (pinfunction "SOURCE_2") (pintype "passive"))
      (node (ref "Q50") (pin "2") (pinfunction "SOURCE_2") (pintype "passive"))
      (node (ref "Q51") (pin "2") (pinfunction "SOURCE_2") (pintype "passive"))
      (node (ref "Q52") (pin "2") (pinfunction "SOURCE_2") (pintype "passive"))
      (node (ref "Q53") (pin "2") (pinfunction "SOURCE_2") (pintype "passive"))
      (node (ref "Q54") (pin "2") (pinfunction "SOURCE_2") (pintype "passive"))
      (node (ref "Q55") (pin "2") (pinfunction "SOURCE_2") (pintype "passive"))
      (node (ref "Q56") (pin "2") (pinfunction "SOURCE_2") (pintype "passive"))
      (node (ref "Q57") (pin "2") (pinfunction "SOURCE_2") (pintype "passive"))
      (node (ref "Q58") (pin "2") (pinfunction "SOURCE_2") (pintype "passive"))
      (node (ref "Q59") (pin "2") (pinfunction "SOURCE_2") (pintype "passive"))
      (node (ref "Q60") (pin "2") (pinfunction "SOURCE_2") (pintype "passive"))
      (node (ref "Q61") (pin "2") (pinfunction "SOURCE_2") (pintype "passive"))
      (node (ref "Q62") (pin "2") (pinfunction "SOURCE_2") (pintype "passive"))
      (node (ref "Q63") (pin "2") (pinfunction "SOURCE_2") (pintype "passive"))
      (node (ref "Q64") (pin "2") (pinfunction "SOURCE_2") (pintype "passive"))
      (node (ref "Q65") (pin "2") (pinfunction "SOURCE_2") (pintype "passive"))
      (node (ref "Q66") (pin "2") (pinfunction "SOURCE_2") (pintype "passive"))
      (node (ref "Q67") (pin "2") (pinfunction "SOURCE_2") (pintype "passive"))
      (node (ref "Q68") (pin "2") (pinfunction "SOURCE_2") (pintype "passive"))
      (node (ref "Q69") (pin "2") (pinfunction "SOURCE_2") (pintype "passive"))
    )
    (net (code "35") (name "Net-(LD56-A)") (class "Default")
      (node (ref "LD56") (pin "1") (pinfunction "A_1") (pintype "passive"))
      (node (ref "R128") (pin "1") (pinfunction "1_1") (pintype "passive"))
    )
    (net (code "36") (name "Net-(LD56-K)") (class "Default")
      (node (ref "LD56") (pin "2") (pinfunction "K_2") (pintype "passive"))
      (node (ref "Q57") (pin "3") (pinfunction "DRAIN_3") (pintype "passive"))
    )
    (net (code "37") (name "Net-(LD57-A)") (class "Default")
      (node (ref "LD57") (pin "1") (pinfunction "A_1") (pintype "passive"))
      (node (ref "R130") (pin "1") (pinfunction "1_1") (pintype "passive"))
    )
    (net (code "38") (name "Net-(LD57-K)") (class "Default")
      (node (ref "LD57") (pin "2") (pinfunction "K_2") (pintype "passive"))
      (node (ref "Q60") (pin "3") (pinfunction "DRAIN_3") (pintype "passive"))
    )
    (net (code "39") (name "Net-(LD58-A)") (class "Default")
      (node (ref "LD58") (pin "1") (pinfunction "A_1") (pintype "passive"))
      (node (ref "R132") (pin "1") (pinfunction "1_1") (pintype "passive"))
    )
    (net (code "40") (name "Net-(LD58-K)") (class "Default")
      (node (ref "LD58") (pin "2") (pinfunction "K_2") (pintype "passive"))
      (node (ref "Q63") (pin "3") (pinfunction "DRAIN_3") (pintype "passive"))
    )
    (net (code "41") (name "Net-(LD59-A)") (class "Default")
      (node (ref "LD59") (pin "1") (pinfunction "A_1") (pintype "passive"))
      (node (ref "R134") (pin "1") (pinfunction "1_1") (pintype "passive"))
    )
    (net (code "42") (name "Net-(LD59-K)") (class "Default")
      (node (ref "LD59") (pin "2") (pinfunction "K_2") (pintype "passive"))
      (node (ref "Q66") (pin "3") (pinfunction "DRAIN_3") (pintype "passive"))
    )
    (net (code "43") (name "Net-(LD60-A)") (class "Default")
      (node (ref "LD60") (pin "1") (pinfunction "A_1") (pintype "passive"))
      (node (ref "R136") (pin "1") (pinfunction "1_1") (pintype "passive"))
    )
    (net (code "44") (name "Net-(LD60-K)") (class "Default")
      (node (ref "LD60") (pin "2") (pinfunction "K_2") (pintype "passive"))
      (node (ref "Q68") (pin "3") (pinfunction "DRAIN_3") (pintype "passive"))
    )
    (net (code "45") (name "Net-(LD61-A)") (class "Default")
      (node (ref "LD61") (pin "1") (pinfunction "A_1") (pintype "passive"))
      (node (ref "R138") (pin "1") (pinfunction "1_1") (pintype "passive"))
    )
    (net (code "46") (name "Net-(LD61-K)") (class "Default")
      (node (ref "LD61") (pin "2") (pinfunction "K_2") (pintype "passive"))
      (node (ref "Q37") (pin "3") (pinfunction "DRAIN_3") (pintype "passive"))
    )
    (net (code "47") (name "Net-(LD62-A)") (class "Default")
      (node (ref "LD62") (pin "1") (pinfunction "A_1") (pintype "passive"))
      (node (ref "R140") (pin "1") (pinfunction "1_1") (pintype "passive"))
    )
    (net (code "48") (name "Net-(LD62-K)") (class "Default")
      (node (ref "LD62") (pin "2") (pinfunction "K_2") (pintype "passive"))
      (node (ref "Q39") (pin "3") (pinfunction "DRAIN_3") (pintype "passive"))
    )
    (net (code "49") (name "Net-(LD63-A)") (class "Default")
      (node (ref "LD63") (pin "1") (pinfunction "A_1") (pintype "passive"))
      (node (ref "R142") (pin "1") (pinfunction "1_1") (pintype "passive"))
    )
    (net (code "50") (name "Net-(LD63-K)") (class "Default")
      (node (ref "LD63") (pin "2") (pinfunction "K_2") (pintype "passive"))
      (node (ref "Q41") (pin "3") (pinfunction "DRAIN_3") (pintype "passive"))
    )
    (net (code "51") (name "Net-(LD64-A)") (class "Default")
      (node (ref "LD64") (pin "1") (pinfunction "A_1") (pintype "passive"))
      (node (ref "R144") (pin "1") (pinfunction "1_1") (pintype "passive"))
    )
    (net (code "52") (name "Net-(LD64-K)") (class "Default")
      (node (ref "LD64") (pin "2") (pinfunction "K_2") (pintype "passive"))
      (node (ref "Q43") (pin "3") (pinfunction "DRAIN_3") (pintype "passive"))
    )
    (net (code "53") (name "Net-(LD65-A)") (class "Default")
      (node (ref "LD65") (pin "1") (pinfunction "A_1") (pintype "passive"))
      (node (ref "R146") (pin "1") (pinfunction "1_1") (pintype "passive"))
    )
    (net (code "54") (name "Net-(LD65-K)") (class "Default")
      (node (ref "LD65") (pin "2") (pinfunction "K_2") (pintype "passive"))
      (node (ref "Q45") (pin "3") (pinfunction "DRAIN_3") (pintype "passive"))
    )
    (net (code "55") (name "Net-(LD66-A)") (class "Default")
      (node (ref "LD66") (pin "1") (pinfunction "A_1") (pintype "passive"))
      (node (ref "R148") (pin "1") (pinfunction "1_1") (pintype "passive"))
    )
    (net (code "56") (name "Net-(LD66-K)") (class "Default")
      (node (ref "LD66") (pin "2") (pinfunction "K_2") (pintype "passive"))
      (node (ref "Q47") (pin "3") (pinfunction "DRAIN_3") (pintype "passive"))
    )
    (net (code "57") (name "Net-(LD67-A)") (class "Default")
      (node (ref "LD67") (pin "1") (pinfunction "A_1") (pintype "passive"))
      (node (ref "R150") (pin "1") (pinfunction "1_1") (pintype "passive"))
    )
    (net (code "58") (name "Net-(LD67-K)") (class "Default")
      (node (ref "LD67") (pin "2") (pinfunction "K_2") (pintype "passive"))
      (node (ref "Q49") (pin "3") (pinfunction "DRAIN_3") (pintype "passive"))
    )
    (net (code "59") (name "Net-(LD68-A)") (class "Default")
      (node (ref "LD68") (pin "1") (pinfunction "A_1") (pintype "passive"))
      (node (ref "R152") (pin "1") (pinfunction "1_1") (pintype "passive"))
    )
    (net (code "60") (name "Net-(LD68-K)") (class "Default")
      (node (ref "LD68") (pin "2") (pinfunction "K_2") (pintype "passive"))
      (node (ref "Q51") (pin "3") (pinfunction "DRAIN_3") (pintype "passive"))
    )
    (net (code "61") (name "Net-(LD69-A)") (class "Default")
      (node (ref "LD69") (pin "1") (pinfunction "A_1") (pintype "passive"))
      (node (ref "R154") (pin "1") (pinfunction "1_1") (pintype "passive"))
    )
    (net (code "62") (name "Net-(LD69-K)") (class "Default")
      (node (ref "LD69") (pin "2") (pinfunction "K_2") (pintype "passive"))
      (node (ref "Q53") (pin "3") (pinfunction "DRAIN_3") (pintype "passive"))
    )
    (net (code "63") (name "Net-(LD70-A)") (class "Default")
      (node (ref "LD70") (pin "1") (pinfunction "A_1") (pintype "passive"))
      (node (ref "R156") (pin "1") (pinfunction "1_1") (pintype "passive"))
    )
    (net (code "64") (name "Net-(LD70-K)") (class "Default")
      (node (ref "LD70") (pin "2") (pinfunction "K_2") (pintype "passive"))
      (node (ref "Q55") (pin "3") (pinfunction "DRAIN_3") (pintype "passive"))
    )
    (net (code "65") (name "Net-(LD71-A)") (class "Default")
      (node (ref "LD71") (pin "1") (pinfunction "A_1") (pintype "passive"))
      (node (ref "R158") (pin "1") (pinfunction "1_1") (pintype "passive"))
    )
    (net (code "66") (name "Net-(LD71-K)") (class "Default")
      (node (ref "LD71") (pin "2") (pinfunction "K_2") (pintype "passive"))
      (node (ref "Q58") (pin "3") (pinfunction "DRAIN_3") (pintype "passive"))
    )
    (net (code "67") (name "Net-(LD72-A)") (class "Default")
      (node (ref "LD72") (pin "1") (pinfunction "A_1") (pintype "passive"))
      (node (ref "R160") (pin "1") (pinfunction "1_1") (pintype "passive"))
    )
    (net (code "68") (name "Net-(LD72-K)") (class "Default")
      (node (ref "LD72") (pin "2") (pinfunction "K_2") (pintype "passive"))
      (node (ref "Q61") (pin "3") (pinfunction "DRAIN_3") (pintype "passive"))
    )
    (net (code "69") (name "Net-(LD73-A)") (class "Default")
      (node (ref "LD73") (pin "1") (pinfunction "A_1") (pintype "passive"))
      (node (ref "R162") (pin "1") (pinfunction "1_1") (pintype "passive"))
    )
    (net (code "70") (name "Net-(LD73-K)") (class "Default")
      (node (ref "LD73") (pin "2") (pinfunction "K_2") (pintype "passive"))
      (node (ref "Q64") (pin "3") (pinfunction "DRAIN_3") (pintype "passive"))
    )
    (net (code "71") (name "Net-(LD74-A)") (class "Default")
      (node (ref "LD74") (pin "1") (pinfunction "A_1") (pintype "passive"))
      (node (ref "R164") (pin "1") (pinfunction "1_1") (pintype "passive"))
    )
    (net (code "72") (name "Net-(LD74-K)") (class "Default")
      (node (ref "LD74") (pin "2") (pinfunction "K_2") (pintype "passive"))
      (node (ref "Q67") (pin "3") (pinfunction "DRAIN_3") (pintype "passive"))
    )
    (net (code "73") (name "Net-(LD75-A)") (class "Default")
      (node (ref "LD75") (pin "1") (pinfunction "A_1") (pintype "passive"))
      (node (ref "R166") (pin "1") (pinfunction "1_1") (pintype "passive"))
    )
    (net (code "74") (name "Net-(LD75-K)") (class "Default")
      (node (ref "LD75") (pin "2") (pinfunction "K_2") (pintype "passive"))
      (node (ref "Q69") (pin "3") (pinfunction "DRAIN_3") (pintype "passive"))
    )
    (net (code "75") (name "Net-(LD76-A)") (class "Default")
      (node (ref "LD76") (pin "1") (pinfunction "A_1") (pintype "passive"))
      (node (ref "R168") (pin "1") (pinfunction "1_1") (pintype "passive"))
    )
    (net (code "76") (name "Net-(LD76-K)") (class "Default")
      (node (ref "LD76") (pin "2") (pinfunction "K_2") (pintype "passive"))
      (node (ref "Q38") (pin "3") (pinfunction "DRAIN_3") (pintype "passive"))
    )
    (net (code "77") (name "Net-(LD77-A)") (class "Default")
      (node (ref "LD77") (pin "1") (pinfunction "A_1") (pintype "passive"))
      (node (ref "R170") (pin "1") (pinfunction "1_1") (pintype "passive"))
    )
    (net (code "78") (name "Net-(LD77-K)") (class "Default")
      (node (ref "LD77") (pin "2") (pinfunction "K_2") (pintype "passive"))
      (node (ref "Q40") (pin "3") (pinfunction "DRAIN_3") (pintype "passive"))
    )
    (net (code "79") (name "Net-(LD78-A)") (class "Default")
      (node (ref "LD78") (pin "1") (pinfunction "A_1") (pintype "passive"))
      (node (ref "R172") (pin "1") (pinfunction "1_1") (pintype "passive"))
    )
    (net (code "80") (name "Net-(LD78-K)") (class "Default")
      (node (ref "LD78") (pin "2") (pinfunction "K_2") (pintype "passive"))
      (node (ref "Q42") (pin "3") (pinfunction "DRAIN_3") (pintype "passive"))
    )
    (net (code "81") (name "Net-(LD79-A)") (class "Default")
      (node (ref "LD79") (pin "1") (pinfunction "A_1") (pintype "passive"))
      (node (ref "R174") (pin "1") (pinfunction "1_1") (pintype "passive"))
    )
    (net (code "82") (name "Net-(LD79-K)") (class "Default")
      (node (ref "LD79") (pin "2") (pinfunction "K_2") (pintype "passive"))
      (node (ref "Q44") (pin "3") (pinfunction "DRAIN_3") (pintype "passive"))
    )
    (net (code "83") (name "Net-(LD80-A)") (class "Default")
      (node (ref "LD80") (pin "1") (pinfunction "A_1") (pintype "passive"))
      (node (ref "R176") (pin "1") (pinfunction "1_1") (pintype "passive"))
    )
    (net (code "84") (name "Net-(LD80-K)") (class "Default")
      (node (ref "LD80") (pin "2") (pinfunction "K_2") (pintype "passive"))
      (node (ref "Q46") (pin "3") (pinfunction "DRAIN_3") (pintype "passive"))
    )
    (net (code "85") (name "Net-(LD81-A)") (class "Default")
      (node (ref "LD81") (pin "1") (pinfunction "A_1") (pintype "passive"))
      (node (ref "R178") (pin "1") (pinfunction "1_1") (pintype "passive"))
    )
    (net (code "86") (name "Net-(LD81-K)") (class "Default")
      (node (ref "LD81") (pin "2") (pinfunction "K_2") (pintype "passive"))
      (node (ref "Q48") (pin "3") (pinfunction "DRAIN_3") (pintype "passive"))
    )
    (net (code "87") (name "Net-(LD82-A)") (class "Default")
      (node (ref "LD82") (pin "1") (pinfunction "A_1") (pintype "passive"))
      (node (ref "R180") (pin "1") (pinfunction "1_1") (pintype "passive"))
    )
    (net (code "88") (name "Net-(LD82-K)") (class "Default")
      (node (ref "LD82") (pin "2") (pinfunction "K_2") (pintype "passive"))
      (node (ref "Q50") (pin "3") (pinfunction "DRAIN_3") (pintype "passive"))
    )
    (net (code "89") (name "Net-(LD83-A)") (class "Default")
      (node (ref "LD83") (pin "1") (pinfunction "A_1") (pintype "passive"))
      (node (ref "R182") (pin "1") (pinfunction "1_1") (pintype "passive"))
    )
    (net (code "90") (name "Net-(LD83-K)") (class "Default")
      (node (ref "LD83") (pin "2") (pinfunction "K_2") (pintype "passive"))
      (node (ref "Q52") (pin "3") (pinfunction "DRAIN_3") (pintype "passive"))
    )
    (net (code "91") (name "Net-(LD84-A)") (class "Default")
      (node (ref "LD84") (pin "1") (pinfunction "A_1") (pintype "passive"))
      (node (ref "R184") (pin "1") (pinfunction "1_1") (pintype "passive"))
    )
    (net (code "92") (name "Net-(LD84-K)") (class "Default")
      (node (ref "LD84") (pin "2") (pinfunction "K_2") (pintype "passive"))
      (node (ref "Q54") (pin "3") (pinfunction "DRAIN_3") (pintype "passive"))
    )
    (net (code "93") (name "Net-(LD85-A)") (class "Default")
      (node (ref "LD85") (pin "1") (pinfunction "A_1") (pintype "passive"))
      (node (ref "R186") (pin "1") (pinfunction "1_1") (pintype "passive"))
    )
    (net (code "94") (name "Net-(LD85-K)") (class "Default")
      (node (ref "LD85") (pin "2") (pinfunction "K_2") (pintype "passive"))
      (node (ref "Q56") (pin "3") (pinfunction "DRAIN_3") (pintype "passive"))
    )
    (net (code "95") (name "Net-(LD86-A)") (class "Default")
      (node (ref "LD86") (pin "1") (pinfunction "A_1") (pintype "passive"))
      (node (ref "R188") (pin "1") (pinfunction "1_1") (pintype "passive"))
    )
    (net (code "96") (name "Net-(LD86-K)") (class "Default")
      (node (ref "LD86") (pin "2") (pinfunction "K_2") (pintype "passive"))
      (node (ref "Q59") (pin "3") (pinfunction "DRAIN_3") (pintype "passive"))
    )
    (net (code "97") (name "Net-(LD87-A)") (class "Default")
      (node (ref "LD87") (pin "1") (pinfunction "A_1") (pintype "passive"))
      (node (ref "R190") (pin "1") (pinfunction "1_1") (pintype "passive"))
    )
    (net (code "98") (name "Net-(LD87-K)") (class "Default")
      (node (ref "LD87") (pin "2") (pinfunction "K_2") (pintype "passive"))
      (node (ref "Q62") (pin "3") (pinfunction "DRAIN_3") (pintype "passive"))
    )
    (net (code "99") (name "Net-(LD88-A)") (class "Default")
      (node (ref "LD88") (pin "1") (pinfunction "A_1") (pintype "passive"))
      (node (ref "R192") (pin "1") (pinfunction "1_1") (pintype "passive"))
    )
    (net (code "100") (name "Net-(LD88-K)") (class "Default")
      (node (ref "LD88") (pin "2") (pinfunction "K_2") (pintype "passive"))
      (node (ref "Q65") (pin "3") (pinfunction "DRAIN_3") (pintype "passive"))
    )
    (net (code "101") (name "Net-(Q37-GATE)") (class "Default")
      (node (ref "Q37") (pin "1") (pinfunction "GATE_1") (pintype "passive"))
      (node (ref "R139") (pin "1") (pinfunction "1_1") (pintype "passive"))
    )
    (net (code "102") (name "Net-(Q38-GATE)") (class "Default")
      (node (ref "Q38") (pin "1") (pinfunction "GATE_1") (pintype "passive"))
      (node (ref "R169") (pin "1") (pinfunction "1_1") (pintype "passive"))
    )
    (net (code "103") (name "Net-(Q39-GATE)") (class "Default")
      (node (ref "Q39") (pin "1") (pinfunction "GATE_1") (pintype "passive"))
      (node (ref "R141") (pin "1") (pinfunction "1_1") (pintype "passive"))
    )
    (net (code "104") (name "Net-(Q40-GATE)") (class "Default")
      (node (ref "Q40") (pin "1") (pinfunction "GATE_1") (pintype "passive"))
      (node (ref "R171") (pin "1") (pinfunction "1_1") (pintype "passive"))
    )
    (net (code "105") (name "Net-(Q41-GATE)") (class "Default")
      (node (ref "Q41") (pin "1") (pinfunction "GATE_1") (pintype "passive"))
      (node (ref "R143") (pin "1") (pinfunction "1_1") (pintype "passive"))
    )
    (net (code "106") (name "Net-(Q42-GATE)") (class "Default")
      (node (ref "Q42") (pin "1") (pinfunction "GATE_1") (pintype "passive"))
      (node (ref "R173") (pin "1") (pinfunction "1_1") (pintype "passive"))
    )
    (net (code "107") (name "Net-(Q43-GATE)") (class "Default")
      (node (ref "Q43") (pin "1") (pinfunction "GATE_1") (pintype "passive"))
      (node (ref "R145") (pin "1") (pinfunction "1_1") (pintype "passive"))
    )
    (net (code "108") (name "Net-(Q44-GATE)") (class "Default")
      (node (ref "Q44") (pin "1") (pinfunction "GATE_1") (pintype "passive"))
      (node (ref "R175") (pin "1") (pinfunction "1_1") (pintype "passive"))
    )
    (net (code "109") (name "Net-(Q45-GATE)") (class "Default")
      (node (ref "Q45") (pin "1") (pinfunction "GATE_1") (pintype "passive"))
      (node (ref "R147") (pin "1") (pinfunction "1_1") (pintype "passive"))
    )
    (net (code "110") (name "Net-(Q46-GATE)") (class "Default")
      (node (ref "Q46") (pin "1") (pinfunction "GATE_1") (pintype "passive"))
      (node (ref "R177") (pin "1") (pinfunction "1_1") (pintype "passive"))
    )
    (net (code "111") (name "Net-(Q47-GATE)") (class "Default")
      (node (ref "Q47") (pin "1") (pinfunction "GATE_1") (pintype "passive"))
      (node (ref "R149") (pin "1") (pinfunction "1_1") (pintype "passive"))
    )
    (net (code "112") (name "Net-(Q48-GATE)") (class "Default")
      (node (ref "Q48") (pin "1") (pinfunction "GATE_1") (pintype "passive"))
      (node (ref "R179") (pin "1") (pinfunction "1_1") (pintype "passive"))
    )
    (net (code "113") (name "Net-(Q49-GATE)") (class "Default")
      (node (ref "Q49") (pin "1") (pinfunction "GATE_1") (pintype "passive"))
      (node (ref "R151") (pin "1") (pinfunction "1_1") (pintype "passive"))
    )
    (net (code "114") (name "Net-(Q50-GATE)") (class "Default")
      (node (ref "Q50") (pin "1") (pinfunction "GATE_1") (pintype "passive"))
      (node (ref "R181") (pin "1") (pinfunction "1_1") (pintype "passive"))
    )
    (net (code "115") (name "Net-(Q51-GATE)") (class "Default")
      (node (ref "Q51") (pin "1") (pinfunction "GATE_1") (pintype "passive"))
      (node (ref "R153") (pin "1") (pinfunction "1_1") (pintype "passive"))
    )
    (net (code "116") (name "Net-(Q52-GATE)") (class "Default")
      (node (ref "Q52") (pin "1") (pinfunction "GATE_1") (pintype "passive"))
      (node (ref "R183") (pin "1") (pinfunction "1_1") (pintype "passive"))
    )
    (net (code "117") (name "Net-(Q53-GATE)") (class "Default")
      (node (ref "Q53") (pin "1") (pinfunction "GATE_1") (pintype "passive"))
      (node (ref "R155") (pin "1") (pinfunction "1_1") (pintype "passive"))
    )
    (net (code "118") (name "Net-(Q54-GATE)") (class "Default")
      (node (ref "Q54") (pin "1") (pinfunction "GATE_1") (pintype "passive"))
      (node (ref "R185") (pin "1") (pinfunction "1_1") (pintype "passive"))
    )
    (net (code "119") (name "Net-(Q55-GATE)") (class "Default")
      (node (ref "Q55") (pin "1") (pinfunction "GATE_1") (pintype "passive"))
      (node (ref "R157") (pin "1") (pinfunction "1_1") (pintype "passive"))
    )
    (net (code "120") (name "Net-(Q56-GATE)") (class "Default")
      (node (ref "Q56") (pin "1") (pinfunction "GATE_1") (pintype "passive"))
      (node (ref "R187") (pin "1") (pinfunction "1_1") (pintype "passive"))
    )
    (net (code "121") (name "Net-(Q57-GATE)") (class "Default")
      (node (ref "Q57") (pin "1") (pinfunction "GATE_1") (pintype "passive"))
      (node (ref "R129") (pin "1") (pinfunction "1_1") (pintype "passive"))
    )
    (net (code "122") (name "Net-(Q58-GATE)") (class "Default")
      (node (ref "Q58") (pin "1") (pinfunction "GATE_1") (pintype "passive"))
      (node (ref "R159") (pin "1") (pinfunction "1_1") (pintype "passive"))
    )
    (net (code "123") (name "Net-(Q59-GATE)") (class "Default")
      (node (ref "Q59") (pin "1") (pinfunction "GATE_1") (pintype "passive"))
      (node (ref "R189") (pin "1") (pinfunction "1_1") (pintype "passive"))
    )
    (net (code "124") (name "Net-(Q60-GATE)") (class "Default")
      (node (ref "Q60") (pin "1") (pinfunction "GATE_1") (pintype "passive"))
      (node (ref "R131") (pin "1") (pinfunction "1_1") (pintype "passive"))
    )
    (net (code "125") (name "Net-(Q61-GATE)") (class "Default")
      (node (ref "Q61") (pin "1") (pinfunction "GATE_1") (pintype "passive"))
      (node (ref "R161") (pin "1") (pinfunction "1_1") (pintype "passive"))
    )
    (net (code "126") (name "Net-(Q62-GATE)") (class "Default")
      (node (ref "Q62") (pin "1") (pinfunction "GATE_1") (pintype "passive"))
      (node (ref "R191") (pin "1") (pinfunction "1_1") (pintype "passive"))
    )
    (net (code "127") (name "Net-(Q63-GATE)") (class "Default")
      (node (ref "Q63") (pin "1") (pinfunction "GATE_1") (pintype "passive"))
      (node (ref "R133") (pin "1") (pinfunction "1_1") (pintype "passive"))
    )
    (net (code "128") (name "Net-(Q64-GATE)") (class "Default")
      (node (ref "Q64") (pin "1") (pinfunction "GATE_1") (pintype "passive"))
      (node (ref "R163") (pin "1") (pinfunction "1_1") (pintype "passive"))
    )
    (net (code "129") (name "Net-(Q65-GATE)") (class "Default")
      (node (ref "Q65") (pin "1") (pinfunction "GATE_1") (pintype "passive"))
      (node (ref "R193") (pin "1") (pinfunction "1_1") (pintype "passive"))
    )
    (net (code "130") (name "Net-(Q66-GATE)") (class "Default")
      (node (ref "Q66") (pin "1") (pinfunction "GATE_1") (pintype "passive"))
      (node (ref "R135") (pin "1") (pinfunction "1_1") (pintype "passive"))
    )
    (net (code "131") (name "Net-(Q67-GATE)") (class "Default")
      (node (ref "Q67") (pin "1") (pinfunction "GATE_1") (pintype "passive"))
      (node (ref "R165") (pin "1") (pinfunction "1_1") (pintype "passive"))
    )
    (net (code "132") (name "Net-(Q68-GATE)") (class "Default")
      (node (ref "Q68") (pin "1") (pinfunction "GATE_1") (pintype "passive"))
      (node (ref "R137") (pin "1") (pinfunction "1_1") (pintype "passive"))
    )
    (net (code "133") (name "Net-(Q69-GATE)") (class "Default")
      (node (ref "Q69") (pin "1") (pinfunction "GATE_1") (pintype "passive"))
      (node (ref "R167") (pin "1") (pinfunction "1_1") (pintype "passive"))
    )
    (net (code "134") (name "VCC2.5") (class "Default")
      (node (ref "C31") (pin "1") (pintype "passive"))
      (node (ref "P14") (pin "3") (pinfunction "3_3") (pintype "passive"))
      (node (ref "P14") (pin "4") (pinfunction "4_4") (pintype "passive"))
      (node (ref "R128") (pin "2") (pinfunction "2_2") (pintype "passive"))
      (node (ref "R130") (pin "2") (pinfunction "2_2") (pintype "passive"))
      (node (ref "R132") (pin "2") (pinfunction "2_2") (pintype "passive"))
      (node (ref "R134") (pin "2") (pinfunction "2_2") (pintype "passive"))
      (node (ref "R136") (pin "2") (pinfunction "2_2") (pintype "passive"))
      (node (ref "R138") (pin "2") (pinfunction "2_2") (pintype "passive"))
      (node (ref "R140") (pin "2") (pinfunction "2_2") (pintype "passive"))
      (node (ref "R142") (pin "2") (pinfunction "2_2") (pintype "passive"))
      (node (ref "R144") (pin "2") (pinfunction "2_2") (pintype "passive"))
      (node (ref "R146") (pin "2") (pinfunction "2_2") (pintype "passive"))
      (node (ref "R148") (pin "2") (pinfunction "2_2") (pintype "passive"))
      (node (ref "R150") (pin "2") (pinfunction "2_2") (pintype "passive"))
      (node (ref "R152") (pin "2") (pinfunction "2_2") (pintype "passive"))
      (node (ref "R154") (pin "2") (pinfunction "2_2") (pintype "passive"))
      (node (ref "R156") (pin "2") (pinfunction "2_2") (pintype "passive"))
      (node (ref "R158") (pin "2") (pinfunction "2_2") (pintype "passive"))
      (node (ref "R160") (pin "2") (pinfunction "2_2") (pintype "passive"))
      (node (ref "R162") (pin "2") (pinfunction "2_2") (pintype "passive"))
      (node (ref "R164") (pin "2") (pinfunction "2_2") (pintype "passive"))
      (node (ref "R166") (pin "2") (pinfunction "2_2") (pintype "passive"))
      (node (ref "R168") (pin "2") (pinfunction "2_2") (pintype "passive"))
      (node (ref "R170") (pin "2") (pinfunction "2_2") (pintype "passive"))
      (node (ref "R172") (pin "2") (pinfunction "2_2") (pintype "passive"))
      (node (ref "R174") (pin "2") (pinfunction "2_2") (pintype "passive"))
      (node (ref "R176") (pin "2") (pinfunction "2_2") (pintype "passive"))
      (node (ref "R178") (pin "2") (pinfunction "2_2") (pintype "passive"))
      (node (ref "R180") (pin "2") (pinfunction "2_2") (pintype "passive"))
      (node (ref "R182") (pin "2") (pinfunction "2_2") (pintype "passive"))
      (node (ref "R184") (pin "2") (pinfunction "2_2") (pintype "passive"))
      (node (ref "R186") (pin "2") (pinfunction "2_2") (pintype "passive"))
      (node (ref "R188") (pin "2") (pinfunction "2_2") (pintype "passive"))
      (node (ref "R190") (pin "2") (pinfunction "2_2") (pintype "passive"))
      (node (ref "R192") (pin "2") (pinfunction "2_2") (pintype "passive"))
    )
    (net (code "135") (name "unconnected-(P13-Pad3)") (class "Default")
      (node (ref "P13") (pin "3") (pinfunction "3_3") (pintype "passive"))
    )
    (net (code "136") (name "unconnected-(P13-Pad5)") (class "Default")
      (node (ref "P13") (pin "5") (pinfunction "5_5") (pintype "passive"))
    )
    (net (code "137") (name "unconnected-(P13-Pad7)") (class "Default")
      (node (ref "P13") (pin "7") (pinfunction "7_7") (pintype "passive"))
    )
    (net (code "138") (name "unconnected-(P13-Pad9)") (class "Default")
      (node (ref "P13") (pin "9") (pinfunction "9_9") (pintype "passive"))
    )
  )
)
